# lower_traced.net
KiCad netlist of a schematic drawn in EAGLE
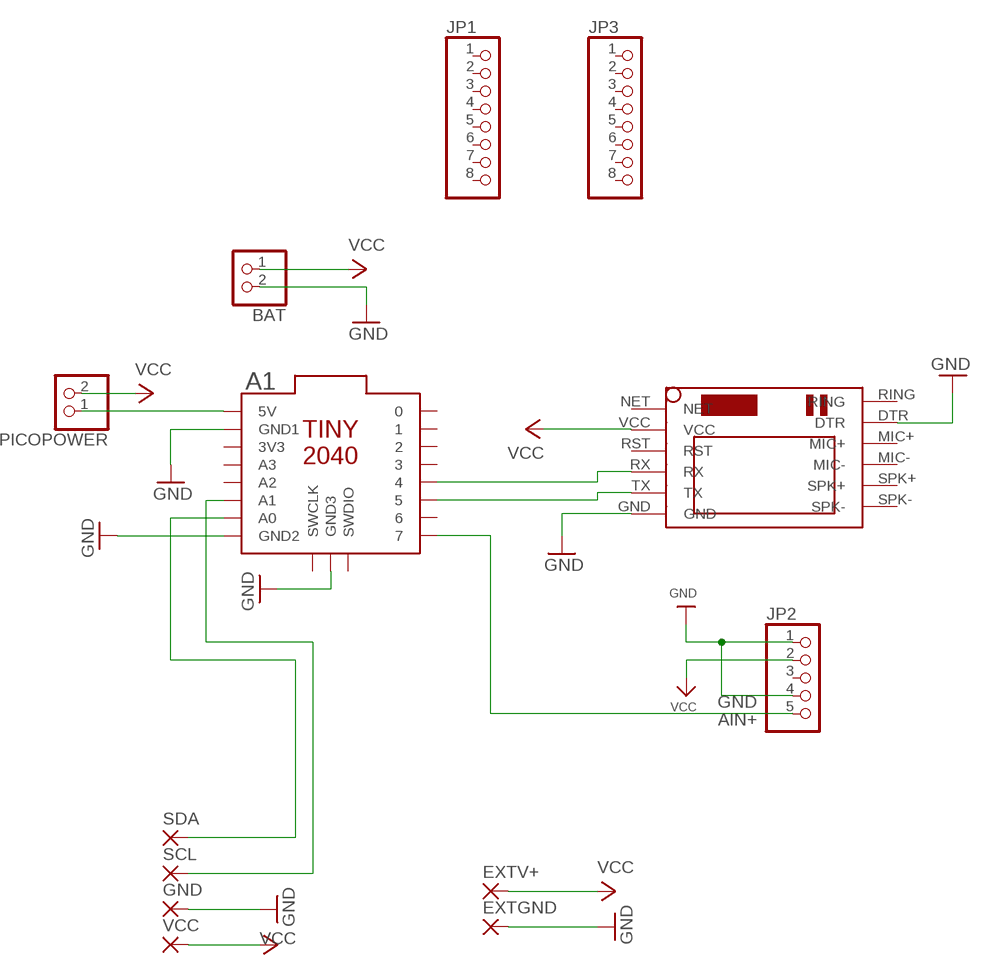
[diagram p0: schematic, sheet 1]

(export (version "E")
  (design (tool "Eeschema 10.0.6"))
  (components
    (comp (ref "A1")
      (value "TINY2040")
      (footprint "eagle-import:TINY2040")
      (libsource (lib "eagle-import") (part "TINY2040"))
    )
    (comp (ref "BAT")
      (value "JST_2PIN-THM-RA")
      (footprint "eagle-import:JST-PH-2-THM-RA")
      (libsource (lib "eagle-import") (part "JST_2PIN-THM-RA"))
    )
    (comp (ref "EXTGND")
      (value "SMD5")
      (footprint "eagle-import:SMD2,54-5,08")
      (libsource (lib "eagle-import") (part "SMD5"))
    )
    (comp (ref "EXTV+")
      (value "SMD5")
      (footprint "eagle-import:SMD2,54-5,08")
      (libsource (lib "eagle-import") (part "SMD5"))
    )
    (comp (ref "GND")
      (value "3,17/1,1")
      (footprint "eagle-import:3,17_1,1")
      (libsource (lib "eagle-import") (part "3,17/1,1"))
    )
    (comp (ref "JP1")
      (value "PINHD-1X8")
      (footprint "eagle-import:1X08")
      (libsource (lib "eagle-import") (part "PINHD-1X8"))
    )
    (comp (ref "JP2")
      (value "HEADER-1X570MIL")
      (footprint "eagle-import:1X05_ROUND_70")
      (libsource (lib "eagle-import") (part "HEADER-1X570MIL"))
    )
    (comp (ref "JP3")
      (value "PINHD-1X8")
      (footprint "eagle-import:1X08")
      (libsource (lib "eagle-import") (part "PINHD-1X8"))
    )
    (comp (ref "PICOPOWER")
      (value "PINHD-1X2")
      (footprint "eagle-import:1X02")
      (libsource (lib "eagle-import") (part "PINHD-1X2"))
    )
    (comp (ref "SCL")
      (value "3,17/1,1")
      (footprint "eagle-import:3,17_1,1")
      (libsource (lib "eagle-import") (part "3,17/1,1"))
    )
    (comp (ref "SDA")
      (value "3,17/1,1")
      (footprint "eagle-import:3,17_1,1")
      (libsource (lib "eagle-import") (part "3,17/1,1"))
    )
    (comp (ref "U$2")
      (value "SIM800LMODULE")
      (footprint "eagle-import:SIM800LMODULE")
      (libsource (lib "eagle-import") (part "SIM800LMODULE"))
    )
    (comp (ref "VCC")
      (value "3,17/1,1")
      (footprint "eagle-import:3,17_1,1")
      (libsource (lib "eagle-import") (part "3,17/1,1"))
    )
  )
  (nets
    (net (code "1") (name "/AIN+") (class "Default")
      (node (ref "A1") (pin "7") (pinfunction "7_7") (pintype "bidirectional"))
      (node (ref "JP2") (pin "5") (pinfunction "5_5") (pintype "passive"))
    )
    (net (code "2") (name "GND") (class "Default")
      (node (ref "A1") (pin "GND1") (pinfunction "GND1_GND1") (pintype "bidirectional"))
      (node (ref "A1") (pin "GND2") (pinfunction "GND2_GND2") (pintype "bidirectional"))
      (node (ref "A1") (pin "GND3") (pinfunction "GND3_GND3") (pintype "bidirectional"))
      (node (ref "BAT") (pin "2") (pinfunction "1_2") (pintype "passive"))
      (node (ref "EXTGND") (pin "1") (pinfunction "P_1") (pintype "passive"))
      (node (ref "GND") (pin "1") (pinfunction "P_1") (pintype "passive"))
      (node (ref "JP2") (pin "1") (pinfunction "1_1") (pintype "passive"))
      (node (ref "JP2") (pin "4") (pinfunction "4_4") (pintype "passive"))
      (node (ref "U$2") (pin "DTR") (pinfunction "DTR_DTR") (pintype "bidirectional"))
      (node (ref "U$2") (pin "GND") (pinfunction "GND_GND") (pintype "bidirectional"))
    )
    (net (code "3") (name "Net-(A1-Pad4)") (class "Default")
      (node (ref "A1") (pin "4") (pinfunction "4_4") (pintype "bidirectional"))
      (node (ref "U$2") (pin "RX") (pinfunction "RX_RX") (pintype "bidirectional"))
    )
    (net (code "4") (name "Net-(A1-Pad5)") (class "Default")
      (node (ref "A1") (pin "5") (pinfunction "5_5") (pintype "bidirectional"))
      (node (ref "U$2") (pin "TX") (pinfunction "TX_TX") (pintype "bidirectional"))
    )
    (net (code "5") (name "Net-(A1-Pad5V)") (class "Default")
      (node (ref "A1") (pin "5V") (pinfunction "5V_5V") (pintype "bidirectional"))
      (node (ref "PICOPOWER") (pin "1") (pinfunction "1_1") (pintype "passive"))
    )
    (net (code "6") (name "Net-(SCL-P)") (class "Default")
      (node (ref "A1") (pin "A1") (pinfunction "A1_A1") (pintype "bidirectional"))
      (node (ref "SCL") (pin "1") (pinfunction "P_1") (pintype "passive"))
    )
    (net (code "7") (name "Net-(SDA-P)") (class "Default")
      (node (ref "A1") (pin "A0") (pinfunction "A0_A0") (pintype "bidirectional"))
      (node (ref "SDA") (pin "1") (pinfunction "P_1") (pintype "passive"))
    )
    (net (code "8") (name "VCC") (class "Default")
      (node (ref "BAT") (pin "1") (pinfunction "2_1") (pintype "passive"))
      (node (ref "EXTV+") (pin "1") (pinfunction "P_1") (pintype "passive"))
      (node (ref "JP2") (pin "2") (pinfunction "2_2") (pintype "passive"))
      (node (ref "PICOPOWER") (pin "2") (pinfunction "2_2") (pintype "passive"))
      (node (ref "U$2") (pin "VCC") (pinfunction "VCC_VCC") (pintype "bidirectional"))
      (node (ref "VCC") (pin "1") (pinfunction "P_1") (pintype "passive"))
    )
    (net (code "9") (name "unconnected-(A1-Pad0)") (class "Default")
      (node (ref "A1") (pin "0") (pinfunction "0_0") (pintype "bidirectional"))
    )
    (net (code "10") (name "unconnected-(A1-Pad1)") (class "Default")
      (node (ref "A1") (pin "1") (pinfunction "1_1") (pintype "bidirectional"))
    )
    (net (code "11") (name "unconnected-(A1-Pad2)") (class "Default")
      (node (ref "A1") (pin "2") (pinfunction "2_2") (pintype "bidirectional"))
    )
    (net (code "12") (name "unconnected-(A1-Pad3)") (class "Default")
      (node (ref "A1") (pin "3") (pinfunction "3_3") (pintype "bidirectional"))
    )
    (net (code "13") (name "unconnected-(A1-Pad3V3)") (class "Default")
      (node (ref "A1") (pin "3V3") (pinfunction "3V3_3V3") (pintype "bidirectional"))
    )
    (net (code "14") (name "unconnected-(A1-Pad6)") (class "Default")
      (node (ref "A1") (pin "6") (pinfunction "6_6") (pintype "bidirectional"))
    )
    (net (code "15") (name "unconnected-(A1-PadA2)") (class "Default")
      (node (ref "A1") (pin "A2") (pinfunction "A2_A2") (pintype "bidirectional"))
    )
    (net (code "16") (name "unconnected-(A1-PadA3)") (class "Default")
      (node (ref "A1") (pin "A3") (pinfunction "A3_A3") (pintype "bidirectional"))
    )
    (net (code "17") (name "unconnected-(A1-PadSWCLK)") (class "Default")
      (node (ref "A1") (pin "SWCLK") (pinfunction "SWCLK_SWCLK") (pintype "bidirectional"))
    )
    (net (code "18") (name "unconnected-(A1-PadSWDIO)") (class "Default")
      (node (ref "A1") (pin "SWDIO") (pinfunction "SWDIO_SWDIO") (pintype "bidirectional"))
    )
    (net (code "19") (name "unconnected-(JP1-Pad1)") (class "Default")
      (node (ref "JP1") (pin "1") (pinfunction "1_1") (pintype "passive"))
    )
    (net (code "20") (name "unconnected-(JP1-Pad2)") (class "Default")
      (node (ref "JP1") (pin "2") (pinfunction "2_2") (pintype "passive"))
    )
    (net (code "21") (name "unconnected-(JP1-Pad3)") (class "Default")
      (node (ref "JP1") (pin "3") (pinfunction "3_3") (pintype "passive"))
    )
    (net (code "22") (name "unconnected-(JP1-Pad4)") (class "Default")
      (node (ref "JP1") (pin "4") (pinfunction "4_4") (pintype "passive"))
    )
    (net (code "23") (name "unconnected-(JP1-Pad5)") (class "Default")
      (node (ref "JP1") (pin "5") (pinfunction "5_5") (pintype "passive"))
    )
    (net (code "24") (name "unconnected-(JP1-Pad6)") (class "Default")
      (node (ref "JP1") (pin "6") (pinfunction "6_6") (pintype "passive"))
    )
    (net (code "25") (name "unconnected-(JP1-Pad7)") (class "Default")
      (node (ref "JP1") (pin "7") (pinfunction "7_7") (pintype "passive"))
    )
    (net (code "26") (name "unconnected-(JP1-Pad8)") (class "Default")
      (node (ref "JP1") (pin "8") (pinfunction "8_8") (pintype "passive"))
    )
    (net (code "27") (name "unconnected-(JP2-Pad3)") (class "Default")
      (node (ref "JP2") (pin "3") (pinfunction "3_3") (pintype "passive"))
    )
    (net (code "28") (name "unconnected-(JP3-Pad1)") (class "Default")
      (node (ref "JP3") (pin "1") (pinfunction "1_1") (pintype "passive"))
    )
    (net (code "29") (name "unconnected-(JP3-Pad2)") (class "Default")
      (node (ref "JP3") (pin "2") (pinfunction "2_2") (pintype "passive"))
    )
    (net (code "30") (name "unconnected-(JP3-Pad3)") (class "Default")
      (node (ref "JP3") (pin "3") (pinfunction "3_3") (pintype "passive"))
    )
    (net (code "31") (name "unconnected-(JP3-Pad4)") (class "Default")
      (node (ref "JP3") (pin "4") (pinfunction "4_4") (pintype "passive"))
    )
    (net (code "32") (name "unconnected-(JP3-Pad5)") (class "Default")
      (node (ref "JP3") (pin "5") (pinfunction "5_5") (pintype "passive"))
    )
    (net (code "33") (name "unconnected-(JP3-Pad6)") (class "Default")
      (node (ref "JP3") (pin "6") (pinfunction "6_6") (pintype "passive"))
    )
    (net (code "34") (name "unconnected-(JP3-Pad7)") (class "Default")
      (node (ref "JP3") (pin "7") (pinfunction "7_7") (pintype "passive"))
    )
    (net (code "35") (name "unconnected-(JP3-Pad8)") (class "Default")
      (node (ref "JP3") (pin "8") (pinfunction "8_8") (pintype "passive"))
    )
    (net (code "36") (name "unconnected-(U$2-PadMIC+)") (class "Default")
      (node (ref "U$2") (pin "MIC+") (pinfunction "MIC+_MIC+") (pintype "bidirectional"))
    )
    (net (code "37") (name "unconnected-(U$2-PadMIC-)") (class "Default")
      (node (ref "U$2") (pin "MIC-") (pinfunction "MIC-_MIC-") (pintype "bidirectional"))
    )
    (net (code "38") (name "unconnected-(U$2-PadNET)") (class "Default")
      (node (ref "U$2") (pin "NET") (pinfunction "NET_NET") (pintype "bidirectional"))
    )
    (net (code "39") (name "unconnected-(U$2-PadRING)") (class "Default")
      (node (ref "U$2") (pin "RING") (pinfunction "RING_RING") (pintype "bidirectional"))
    )
    (net (code "40") (name "unconnected-(U$2-PadRST)") (class "Default")
      (node (ref "U$2") (pin "RST") (pinfunction "RST_RST") (pintype "bidirectional"))
    )
    (net (code "41") (name "unconnected-(U$2-PadSPK+)") (class "Default")
      (node (ref "U$2") (pin "SPK+") (pinfunction "SPK+_SPK+") (pintype "bidirectional"))
    )
    (net (code "42") (name "unconnected-(U$2-PadSPK-)") (class "Default")
      (node (ref "U$2") (pin "SPK-") (pinfunction "SPK-_SPK-") (pintype "bidirectional"))
    )
  )
)
